# Power_Management.net
KiCad netlist of a schematic drawn in Altium Designer
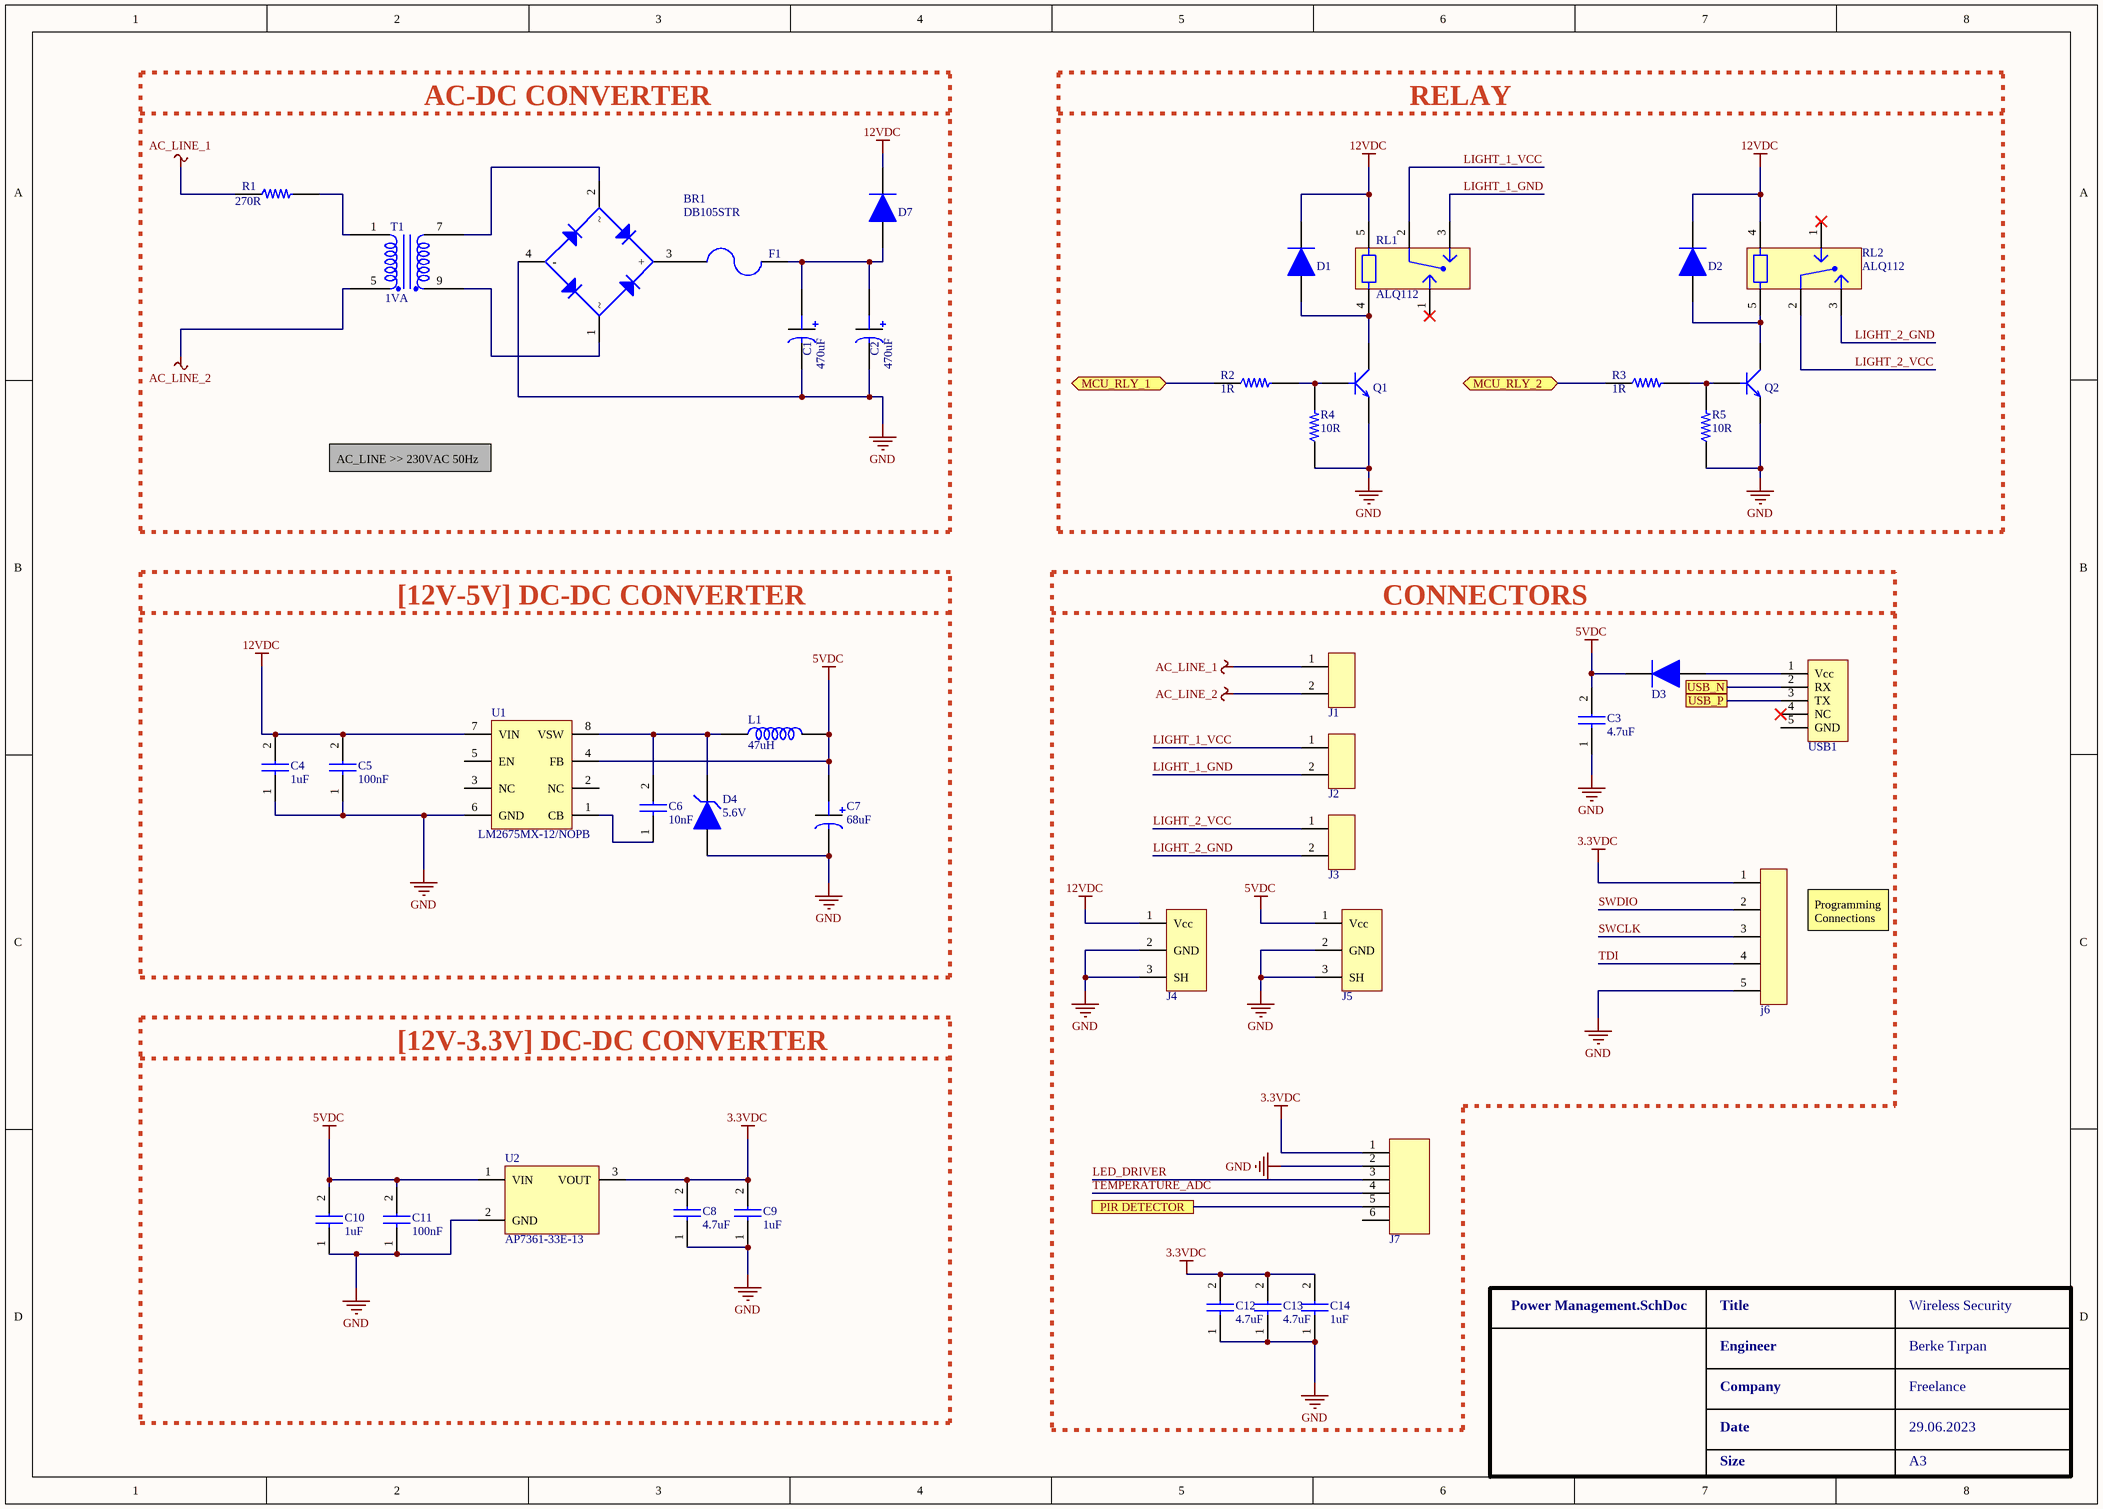
[diagram p0: Power Management.SchDoc]

(export (version "E")
  (design (tool "Eeschema 10.0.6"))
  (components
    (comp (ref "BR1")
      (value "DB105STR")
      (footprint "DB105STR")
      (description "Bridge Rect 1PHASE 600V 1A Db-s")
      (fields
        (field (name "MANUFACTURER") "Sangdest Microelectronics")
        (field (name "MANUFACTURER PART NUMBER") "DB105S")
      )
      (libsource (lib "Ilk Proje") (part "DB105STR"))
    )
    (comp (ref "C1")
      (value "ESH477M050AH4AA")
      (footprint "CAP_RADIAL_D10_P5")
      (description "Cap, 470UF, 50V, Alu Elec, Radial")
      (fields
        (field (name "MANUFACTURER") "KEMET")
        (field (name "TOLERANCE") "20%")
        (field (name "CAPACITANCE") "470uF")
      )
      (libsource (lib "Ilk Proje") (part "CAP ALU ELEC 470.UF 50V"))
    )
    (comp (ref "C2")
      (value "ESH477M050AH4AA")
      (footprint "CAP_RADIAL_D10_P5")
      (description "Cap, 470UF, 50V, Alu Elec, Radial")
      (fields
        (field (name "MANUFACTURER") "KEMET")
        (field (name "TOLERANCE") "20%")
        (field (name "CAPACITANCE") "470uF")
      )
      (libsource (lib "Ilk Proje") (part "CAP ALU ELEC 470.UF 50V"))
    )
    (comp (ref "C3")
      (value "CAP_CER_4,7UF_0805")
      (footprint "CAP_0805")
      (description "CAP CER 4.7UF 25V %10 0805")
      (fields
        (field (name "MANUFACTURER") "Samsung")
        (field (name "MANUFACTURER PART NUMBER") "CL21A475KAQNNNE")
        (field (name "CAPACITANCE") "4.7uF")
      )
      (libsource (lib "Ilk Proje") (part "CAP_CER_4,7UF_0805"))
    )
    (comp (ref "C4")
      (value "CAP CER 1uF 0805")
      (footprint "CAP_0805")
      (description "CAP CER 1UF 50V X7R %10 0805")
      (fields
        (field (name "MANUFACTURER") "Samsung")
        (field (name "MANUFACTURER PART NUMBER") "CL21B105KBFNNNE")
        (field (name "CAPACITANCE") "1uF")
      )
      (libsource (lib "Ilk Proje") (part "CAP CER 1uF 0805"))
    )
    (comp (ref "C5")
      (value "CAP CER 100nF 0805")
      (footprint "CAP_0805")
      (description "CAP CER 0.1UF 50V X7R 0805")
      (fields
        (field (name "MANUFACTURER") "Samsung")
        (field (name "MANUFACTURER PART NUMBER") "CL21B104KBCNNNC")
        (field (name "CAPACITANCE") "100nF")
      )
      (libsource (lib "Ilk Proje") (part "CAP CER 100nF 0805"))
    )
    (comp (ref "C6")
      (value "CAP CER 10nF 0603")
      (footprint "CAP_0603")
      (description "Multilayer Ceramic Capacitor, 0.01 F, 10%, X7R, 16 V, 0603 [1608 Metric] RoHS Compliant: Yes")
      (fields
        (field (name "MANUFACTURER") "Walsin Technologies")
        (field (name "MANUFACTURER PART NUMBER") "0603B103K160CT")
        (field (name "CAPACITANCE") "10nF")
      )
      (libsource (lib "Ilk Proje") (part "CAP CER 10nF 0603"))
    )
    (comp (ref "C7")
      (value "EEV686M035A9HAA")
      (footprint "CAP_EEVSERIES")
      (description "Cap Aluminum Lytic 68uF 35V 20% (6.3 X 7.7mm) SMD 280mA 2000h 105C T/R")
      (fields
        (field (name "MANUFACTURER") "KEMET")
        (field (name "TOLERANCE") "20%")
        (field (name "CAPACITANCE") "68uF")
      )
      (libsource (lib "Ilk Proje") (part "CAP ALU 68uF"))
    )
    (comp (ref "C8")
      (value "CAP_CER_4,7UF_0805")
      (footprint "CAP_0805")
      (description "CAP CER 4.7UF 25V %10 0805")
      (fields
        (field (name "MANUFACTURER") "Samsung")
        (field (name "MANUFACTURER PART NUMBER") "CL21A475KAQNNNE")
        (field (name "CAPACITANCE") "4.7uF")
      )
      (libsource (lib "Ilk Proje") (part "CAP_CER_4,7UF_0805"))
    )
    (comp (ref "C9")
      (value "CAP CER 1uF 0805")
      (footprint "CAP_0805")
      (description "CAP CER 1UF 50V X7R %10 0805")
      (fields
        (field (name "MANUFACTURER") "Samsung")
        (field (name "MANUFACTURER PART NUMBER") "CL21B105KBFNNNE")
        (field (name "CAPACITANCE") "1uF")
      )
      (libsource (lib "Ilk Proje") (part "CAP CER 1uF 0805"))
    )
    (comp (ref "C10")
      (value "CAP CER 1uF 0805")
      (footprint "CAP_0805")
      (description "CAP CER 1UF 50V X7R %10 0805")
      (fields
        (field (name "MANUFACTURER") "Samsung")
        (field (name "MANUFACTURER PART NUMBER") "CL21B105KBFNNNE")
        (field (name "CAPACITANCE") "1uF")
      )
      (libsource (lib "Ilk Proje") (part "CAP CER 1uF 0805"))
    )
    (comp (ref "C11")
      (value "C0603C104K5RACTU")
      (footprint "CAP_0603")
      (description "Multilayer Ceramic Capacitors (MLCC) - SMD/SMT 50volts 0.1uF X7R 10%")
      (fields
        (field (name "MANUFACTURER") "KEMET")
        (field (name "TOLERANCE") "10%")
        (field (name "CAPACITANCE") "100nF")
      )
      (libsource (lib "Ilk Proje") (part "CAP CER 100nF 0603"))
    )
    (comp (ref "C12")
      (value "CAP_CER_4,7UF_0805")
      (footprint "CAP_0805")
      (description "CAP CER 4.7UF 25V %10 0805")
      (fields
        (field (name "MANUFACTURER") "Samsung")
        (field (name "MANUFACTURER PART NUMBER") "CL21A475KAQNNNE")
        (field (name "CAPACITANCE") "4.7uF")
      )
      (libsource (lib "Ilk Proje") (part "CAP_CER_4,7UF_0805"))
    )
    (comp (ref "C13")
      (value "CAP_CER_4,7UF_0805")
      (footprint "CAP_0805")
      (description "CAP CER 4.7UF 25V %10 0805")
      (fields
        (field (name "MANUFACTURER") "Samsung")
        (field (name "MANUFACTURER PART NUMBER") "CL21A475KAQNNNE")
        (field (name "CAPACITANCE") "4.7uF")
      )
      (libsource (lib "Ilk Proje") (part "CAP_CER_4,7UF_0805"))
    )
    (comp (ref "C14")
      (value "CAP CER 1uF 0805")
      (footprint "CAP_0805")
      (description "CAP CER 1UF 50V X7R %10 0805")
      (fields
        (field (name "MANUFACTURER") "Samsung")
        (field (name "MANUFACTURER PART NUMBER") "CL21B105KBFNNNE")
        (field (name "CAPACITANCE") "1uF")
      )
      (libsource (lib "Ilk Proje") (part "CAP CER 1uF 0805"))
    )
    (comp (ref "D1")
      (value "1N4148WS")
      (footprint "SOD323F")
      (description "VR=75V IF=150mA Trr=4ns P=200mW")
      (fields (field (name "MANUFACTURER") "ON Semiconductor / Fairchild"))
      (libsource (lib "Ilk Proje") (part "1N4148WS"))
    )
    (comp (ref "D2")
      (value "1N4148WS")
      (footprint "SOD323F")
      (description "VR=75V IF=150mA Trr=4ns P=200mW")
      (fields (field (name "MANUFACTURER") "ON Semiconductor / Fairchild"))
      (libsource (lib "Ilk Proje") (part "1N4148WS"))
    )
    (comp (ref "D3")
      (value "1N4148WS")
      (footprint "SOD323F")
      (description "VR=75V IF=150mA Trr=4ns P=200mW")
      (fields (field (name "MANUFACTURER") "ON Semiconductor / Fairchild"))
      (libsource (lib "Ilk Proje") (part "1N4148WS"))
    )
    (comp (ref "D4")
      (value "1SMB5919BT3G")
      (footprint "SMB")
      (description "Vz=5.6V 5.32V~5.88V Izt=66.9mA")
      (fields
        (field (name "MANUFACTURER") "ON Semiconductor")
        (field (name "TOLERANCE") "5%")
        (field (name "ZENER VOLTAGE") "5.6V")
      )
      (libsource (lib "Ilk Proje") (part "1SMB5919BT3G"))
    )
    (comp (ref "D7")
      (value "1N4148WS")
      (footprint "SOD323F")
      (description "VR=75V IF=150mA Trr=4ns P=200mW")
      (fields (field (name "MANUFACTURER") "ON Semiconductor / Fairchild"))
      (libsource (lib "Ilk Proje") (part "1N4148WS"))
    )
    (comp (ref "F1")
      (value "FUSE 3413.0216.22")
      (footprint "3413.0216.22")
      (description "Fuse Chip Fast Acting 1A 32V SMD Solder Pad 1206 Glass T/R VDE/cULus")
      (fields
        (field (name "MANUFACTURER") "Schurter")
        (field (name "MANUFACTURER PART NUMBER") "3413.0216.22")
      )
      (libsource (lib "Ilk Proje") (part "FUSE 3413.0216.22"))
    )
    (comp (ref "J1")
      (value "TBP01R1-508-02BE")
      (footprint "TBP01R1-508")
      (description "2~24 Poles, Pluggable, Receptacle, Horizontal, 5.08 Pitch, Terminal Block Connector")
      (fields (field (name "MANUFACTURER") "CUI"))
      (libsource (lib "Ilk Proje") (part "TBP01R1-508-02BE"))
    )
    (comp (ref "J2")
      (value "TBP01R1-508-02BE")
      (footprint "TBP01R1-508")
      (description "2~24 Poles, Pluggable, Receptacle, Horizontal, 5.08 Pitch, Terminal Block Connector")
      (fields (field (name "MANUFACTURER") "CUI"))
      (libsource (lib "Ilk Proje") (part "TBP01R1-508-02BE"))
    )
    (comp (ref "J3")
      (value "TBP01R1-508-02BE")
      (footprint "TBP01R1-508")
      (description "2~24 Poles, Pluggable, Receptacle, Horizontal, 5.08 Pitch, Terminal Block Connector")
      (fields (field (name "MANUFACTURER") "CUI"))
      (libsource (lib "Ilk Proje") (part "TBP01R1-508-02BE"))
    )
    (comp (ref "J4")
      (value "PJ-037AH-SMT-TR")
      (footprint "JACK")
      (description "2.0 x 6.3 mm, 5.0 A, Horizontal, Surface Mount (SMT), Dc Power Jack Connector")
      (fields (field (name "MANUFACTURER") "CUI"))
      (libsource (lib "Ilk Proje") (part "PJ-037AH-SMT-TR"))
    )
    (comp (ref "J5")
      (value "PJ-037AH-SMT-TR")
      (footprint "JACK")
      (description "2.0 x 6.3 mm, 5.0 A, Horizontal, Surface Mount (SMT), Dc Power Jack Connector")
      (fields (field (name "MANUFACTURER") "CUI"))
      (libsource (lib "Ilk Proje") (part "PJ-037AH-SMT-TR"))
    )
    (comp (ref "j6")
      (value "SMH-105-02-L-S")
      (footprint "PINHEADER1X5_RA")
      (description ".100 C.L. HORIZONTAL SMT SOCKET")
      (fields (field (name "MANUFACTURER") "Samtec"))
      (libsource (lib "Ilk Proje") (part "SMH-105-02-L-S"))
    )
    (comp (ref "J7")
      (value "64800611622")
      (footprint "64800611622")
      (description "WR-WTB Wire-to-Board Connectors 6PIN 1.50 mm")
      (fields (field (name "MANUFACTURER") "Wurth Electronics"))
      (libsource (lib "Ilk Proje") (part "64800611622_conn_6pin"))
    )
    (comp (ref "L1")
      (value "78438335470")
      (footprint "IND_1212")
      (description "Power Inductor, Aec-Q200, 47Uh, 0.39A Rohs Compliant: Yes ¦Wurth Elektronik 78438335470")
      (fields
        (field (name "MANUFACTURER") "Wurth Electronics")
        (field (name "TOLERANCE") "30%")
        (field (name "INDUCTANCE") "47uH")
      )
      (libsource (lib "Ilk Proje") (part "IND 47uH"))
    )
    (comp (ref "Q1")
      (value "MMBT3904-7-F")
      (footprint "SOT23-F")
      (description "NPN Ic=200mA Vceo=40V hfe=100~300 fT=310MHz P=300mW SOT-23")
      (fields (field (name "MANUFACTURER") "Diodes Zetex"))
      (libsource (lib "Ilk Proje") (part "MMBT3904-7-F"))
    )
    (comp (ref "Q2")
      (value "MMBT3904-7-F")
      (footprint "SOT23-F")
      (description "NPN Ic=200mA Vceo=40V hfe=100~300 fT=310MHz P=300mW SOT-23")
      (fields (field (name "MANUFACTURER") "Diodes Zetex"))
      (libsource (lib "Ilk Proje") (part "MMBT3904-7-F"))
    )
    (comp (ref "R1")
      (value "5WD27")
      (footprint "RES_AXIAL_W")
      (description "RES 0.27 OHM 5% 5W AXIAL")
      (fields
        (field (name "MFR") "NTE Electronics, Inc")
        (field (name "TOLERANCE") "±5%")
        (field (name "RESISTANCE") "270R")
      )
      (libsource (lib "Ilk Proje") (part "5WD27"))
    )
    (comp (ref "R2")
      (value "RT0603BRD071KL")
      (footprint "RES_0603")
      (description "High Precision-High Stability Chip Resistor Thin Film 0603 1kOhm 0.1% Paper T/R")
      (fields (field (name "MANUFACTURER") "Yageo") (field (name "RESISTANCE") "1R"))
      (libsource (lib "Ilk Proje") (part "RES 1K OHM 0603"))
    )
    (comp (ref "R3")
      (value "RT0603BRD071KL")
      (footprint "RES_0603")
      (description "High Precision-High Stability Chip Resistor Thin Film 0603 1kOhm 0.1% Paper T/R")
      (fields (field (name "MANUFACTURER") "Yageo") (field (name "RESISTANCE") "1R"))
      (libsource (lib "Ilk Proje") (part "RES 1K OHM 0603"))
    )
    (comp (ref "R4")
      (value "RC0603FR-0710KL")
      (footprint "RES_0603")
      (description "RES SMD 10K OHM 1% 1/10W 0603")
      (fields
        (field (name "MANUFACTURER") "Yageo")
        (field (name "TOLERANCE") "1%")
        (field (name "RESISTANCE") "10R")
      )
      (libsource (lib "Ilk Proje") (part "RES 10K OHM 0603"))
    )
    (comp (ref "R5")
      (value "RC0603FR-0710KL")
      (footprint "RES_0603")
      (description "RES SMD 10K OHM 1% 1/10W 0603")
      (fields
        (field (name "MANUFACTURER") "Yageo")
        (field (name "TOLERANCE") "1%")
        (field (name "RESISTANCE") "10R")
      )
      (libsource (lib "Ilk Proje") (part "RES 10K OHM 0603"))
    )
    (comp (ref "RL1")
      (value "ALQ112")
      (footprint "ALQ112")
      (description "General Purpose Relay SPDT (1 Form C) 12VDC Coil Through Hole")
      (fields (field (name "MANUFACTURER") "Panasonic"))
      (libsource (lib "") (part "ALQ112_1"))
    )
    (comp (ref "RL2")
      (value "ALQ112")
      (footprint "ALQ112")
      (description "General Purpose Relay SPDT (1 Form C) 12VDC Coil Through Hole")
      (fields (field (name "MANUFACTURER") "Panasonic"))
      (libsource (lib "Ilk Proje") (part "ALQ112"))
    )
    (comp (ref "T1")
      (value "BV302S12010-ZU")
      (footprint "BV302S12010-ZU")
      (description "230-12V Transformer 1VA")
      (fields (field (name "MANUFACTURER") "Zettler Magnetics") (field (name "RATED POWER") "1VA"))
      (libsource (lib "Ilk Proje") (part "BV302S12010-ZU"))
    )
    (comp (ref "U1")
      (value "LM2675MX-12/NOPB")
      (footprint "SOIC8")
      (description "SIMPLE SWITCHER® 6.5V to 40V, 1A Low Component Count Step-Down Regulator 8-SOIC -40 to 125")
      (fields (field (name "MANUFACTURER") "TI National Semiconductor"))
      (libsource (lib "Ilk Proje") (part "LM2675MX-12/NOPB"))
    )
    (comp (ref "U2")
      (value "AP7361-33E-13")
      (footprint "SOT223")
      (description "AP7361 Series 3.3 V 1 A Low SMT Dropout Fixed-Mode Regulator - SOT-223")
      (fields (field (name "MANUFACTURER") "Diodes"))
      (libsource (lib "Ilk Proje") (part "AP7361-33E-13"))
    )
    (comp (ref "USB1")
      (value "10118192-0001LF")
      (footprint "MICRO_B_USB")
      (description "CONN USB MICRO B RECPT SMT R/A")
      (fields (field (name "MANUFACTURER") "Amphenol ICC / FCI"))
      (libsource (lib "Ilk Proje") (part "Micro B USB Connector"))
    )
  )
  (nets
    (net (code "1") (name "/LED_DRIVER") (class "Default") (node (ref "J7") (pin "3") (pintype "power_in")))
    (net (code "2") (name "/LIGHT_1_GND") (class "Default")
      (node (ref "J2") (pin "2") (pinfunction "2_2") (pintype "power_in"))
      (node (ref "RL1") (pin "3") (pinfunction "3_3") (pintype "passive"))
    )
    (net (code "3") (name "/LIGHT_1_VCC") (class "Default")
      (node (ref "J2") (pin "1") (pinfunction "1_1") (pintype "power_in"))
      (node (ref "RL1") (pin "2") (pinfunction "2_2") (pintype "passive"))
    )
    (net (code "4") (name "/LIGHT_2_GND") (class "Default")
      (node (ref "J3") (pin "2") (pinfunction "2_2") (pintype "power_in"))
      (node (ref "RL2") (pin "3") (pinfunction "3_3") (pintype "passive"))
    )
    (net (code "5") (name "/LIGHT_2_VCC") (class "Default")
      (node (ref "J3") (pin "1") (pinfunction "1_1") (pintype "power_in"))
      (node (ref "RL2") (pin "2") (pinfunction "2_2") (pintype "passive"))
    )
    (net (code "6") (name "/MCU_RLY_1") (class "Default")
      (node (ref "R2") (pin "1") (pinfunction "1_1") (pintype "passive"))
    )
    (net (code "7") (name "/MCU_RLY_2") (class "Default")
      (node (ref "R3") (pin "1") (pinfunction "1_1") (pintype "passive"))
    )
    (net (code "8") (name "/PIR DETECTOR") (class "Default") (node (ref "J7") (pin "5") (pintype "power_in")))
    (net (code "9") (name "/SWCLK") (class "Default")
      (node (ref "j6") (pin "3") (pinfunction "3_3") (pintype "power_in"))
    )
    (net (code "10") (name "/SWDIO") (class "Default")
      (node (ref "j6") (pin "2") (pinfunction "2_2") (pintype "power_in"))
    )
    (net (code "11") (name "/TDI") (class "Default")
      (node (ref "j6") (pin "4") (pinfunction "4_4") (pintype "power_in"))
    )
    (net (code "12") (name "/TEMPERATURE_ADC") (class "Default")
      (node (ref "J7") (pin "4") (pintype "power_in"))
    )
    (net (code "13") (name "/USB_N") (class "Default")
      (node (ref "USB1") (pin "2") (pinfunction "RX_2") (pintype "power_in"))
    )
    (net (code "14") (name "/USB_P") (class "Default")
      (node (ref "USB1") (pin "3") (pinfunction "TX_3") (pintype "power_in"))
    )
    (net (code "15") (name "3.3VDC") (class "Default")
      (node (ref "C12") (pin "2") (pinfunction "2_2") (pintype "passive"))
      (node (ref "C13") (pin "2") (pinfunction "2_2") (pintype "passive"))
      (node (ref "C14") (pin "2") (pinfunction "2_2") (pintype "passive"))
      (node (ref "C8") (pin "2") (pinfunction "2_2") (pintype "passive"))
      (node (ref "C9") (pin "2") (pinfunction "2_2") (pintype "passive"))
      (node (ref "J7") (pin "1") (pintype "power_in"))
      (node (ref "U2") (pin "3") (pinfunction "VOUT_3") (pintype "passive"))
      (node (ref "j6") (pin "1") (pinfunction "1_1") (pintype "power_in"))
    )
    (net (code "16") (name "5VDC") (class "Default")
      (node (ref "C10") (pin "2") (pinfunction "2_2") (pintype "passive"))
      (node (ref "C11") (pin "2") (pinfunction "2_2") (pintype "passive"))
      (node (ref "C3") (pin "2") (pinfunction "2_2") (pintype "passive"))
      (node (ref "C7") (pin "1") (pinfunction "1_1") (pintype "passive"))
      (node (ref "D3") (pin "1") (pinfunction "1_1") (pintype "power_in"))
      (node (ref "J5") (pin "1") (pinfunction "Vcc_1") (pintype "passive"))
      (node (ref "L1") (pin "2") (pinfunction "2_2") (pintype "passive"))
      (node (ref "U1") (pin "4") (pinfunction "FB_4") (pintype "passive"))
      (node (ref "U2") (pin "1") (pinfunction "VIN_1") (pintype "passive"))
    )
    (net (code "17") (name "12VDC") (class "Default")
      (node (ref "C4") (pin "2") (pinfunction "2_2") (pintype "passive"))
      (node (ref "C5") (pin "2") (pinfunction "2_2") (pintype "passive"))
      (node (ref "D1") (pin "1") (pinfunction "1_1") (pintype "power_in"))
      (node (ref "D2") (pin "1") (pinfunction "1_1") (pintype "power_in"))
      (node (ref "D7") (pin "1") (pinfunction "1_1") (pintype "power_in"))
      (node (ref "J4") (pin "1") (pinfunction "Vcc_1") (pintype "passive"))
      (node (ref "RL1") (pin "5") (pinfunction "5_5") (pintype "passive"))
      (node (ref "RL2") (pin "4") (pinfunction "4_4") (pintype "passive"))
      (node (ref "U1") (pin "7") (pinfunction "VIN_7") (pintype "passive"))
    )
    (net (code "18") (name "AC_LINE_1") (class "Default")
      (node (ref "J1") (pin "1") (pinfunction "1_1") (pintype "power_in"))
      (node (ref "R1") (pin "1") (pinfunction "1_1") (pintype "passive"))
    )
    (net (code "19") (name "AC_LINE_2") (class "Default")
      (node (ref "J1") (pin "2") (pinfunction "2_2") (pintype "power_in"))
      (node (ref "T1") (pin "5") (pinfunction "5_5") (pintype "passive"))
    )
    (net (code "20") (name "GND") (class "Default")
      (node (ref "BR1") (pin "4") (pinfunction "-_4") (pintype "passive"))
      (node (ref "C1") (pin "2") (pinfunction "2_2") (pintype "passive"))
      (node (ref "C10") (pin "1") (pinfunction "1_1") (pintype "passive"))
      (node (ref "C11") (pin "1") (pinfunction "1_1") (pintype "passive"))
      (node (ref "C12") (pin "1") (pinfunction "1_1") (pintype "passive"))
      (node (ref "C13") (pin "1") (pinfunction "1_1") (pintype "passive"))
      (node (ref "C14") (pin "1") (pinfunction "1_1") (pintype "passive"))
      (node (ref "C2") (pin "2") (pinfunction "2_2") (pintype "passive"))
      (node (ref "C3") (pin "1") (pinfunction "1_1") (pintype "passive"))
      (node (ref "C4") (pin "1") (pinfunction "1_1") (pintype "passive"))
      (node (ref "C5") (pin "1") (pinfunction "1_1") (pintype "passive"))
      (node (ref "C7") (pin "2") (pinfunction "2_2") (pintype "passive"))
      (node (ref "C8") (pin "1") (pinfunction "1_1") (pintype "passive"))
      (node (ref "C9") (pin "1") (pinfunction "1_1") (pintype "passive"))
      (node (ref "D4") (pin "A") (pinfunction "A_A") (pintype "passive"))
      (node (ref "J4") (pin "2") (pinfunction "GND_2") (pintype "passive"))
      (node (ref "J4") (pin "3") (pinfunction "SH_3") (pintype "passive"))
      (node (ref "J5") (pin "2") (pinfunction "GND_2") (pintype "passive"))
      (node (ref "J5") (pin "3") (pinfunction "SH_3") (pintype "passive"))
      (node (ref "J7") (pin "2") (pintype "power_in"))
      (node (ref "Q1") (pin "2") (pinfunction "E_2") (pintype "power_in"))
      (node (ref "Q2") (pin "2") (pinfunction "E_2") (pintype "power_in"))
      (node (ref "R4") (pin "1") (pinfunction "1_1") (pintype "passive"))
      (node (ref "R5") (pin "1") (pinfunction "1_1") (pintype "passive"))
      (node (ref "U1") (pin "6") (pinfunction "GND_6") (pintype "passive"))
      (node (ref "U2") (pin "2") (pinfunction "GND_2") (pintype "passive"))
      (node (ref "j6") (pin "5") (pinfunction "5_5") (pintype "power_in"))
    )
    (net (code "21") (name "Net-(BR1-+)") (class "Default")
      (node (ref "BR1") (pin "3") (pinfunction "+_3") (pintype "passive"))
      (node (ref "F1") (pin "1") (pinfunction "1_1") (pintype "passive"))
    )
    (net (code "22") (name "Net-(BR1-~-Pad1)") (class "Default")
      (node (ref "BR1") (pin "1") (pinfunction "~_1") (pintype "passive"))
      (node (ref "T1") (pin "9") (pinfunction "9_9") (pintype "passive"))
    )
    (net (code "23") (name "Net-(BR1-~-Pad2)") (class "Default")
      (node (ref "BR1") (pin "2") (pinfunction "~_2") (pintype "passive"))
      (node (ref "T1") (pin "7") (pinfunction "7_7") (pintype "passive"))
    )
    (net (code "24") (name "Net-(C1-Pad1)") (class "Default")
      (node (ref "C1") (pin "1") (pinfunction "1_1") (pintype "passive"))
      (node (ref "C2") (pin "1") (pinfunction "1_1") (pintype "passive"))
      (node (ref "D7") (pin "2") (pinfunction "2_2") (pintype "power_in"))
      (node (ref "F1") (pin "2") (pinfunction "2_2") (pintype "passive"))
    )
    (net (code "25") (name "Net-(Q1-B)") (class "Default")
      (node (ref "Q1") (pin "1") (pinfunction "B_1") (pintype "power_in"))
      (node (ref "R2") (pin "2") (pinfunction "2_2") (pintype "passive"))
      (node (ref "R4") (pin "2") (pinfunction "2_2") (pintype "passive"))
    )
    (net (code "26") (name "Net-(Q1-C)") (class "Default")
      (node (ref "D1") (pin "2") (pinfunction "2_2") (pintype "power_in"))
      (node (ref "Q1") (pin "3") (pinfunction "C_3") (pintype "power_in"))
      (node (ref "RL1") (pin "4") (pinfunction "4_4") (pintype "passive"))
    )
    (net (code "27") (name "Net-(Q2-B)") (class "Default")
      (node (ref "Q2") (pin "1") (pinfunction "B_1") (pintype "power_in"))
      (node (ref "R3") (pin "2") (pinfunction "2_2") (pintype "passive"))
      (node (ref "R5") (pin "2") (pinfunction "2_2") (pintype "passive"))
    )
    (net (code "28") (name "Net-(Q2-C)") (class "Default")
      (node (ref "D2") (pin "2") (pinfunction "2_2") (pintype "power_in"))
      (node (ref "Q2") (pin "3") (pinfunction "C_3") (pintype "power_in"))
      (node (ref "RL2") (pin "5") (pinfunction "5_5") (pintype "passive"))
    )
    (net (code "29") (name "Net-(R1-Pad2)") (class "Default")
      (node (ref "R1") (pin "2") (pinfunction "2_2") (pintype "passive"))
      (node (ref "T1") (pin "1") (pinfunction "1_1") (pintype "passive"))
    )
    (net (code "30") (name "Net-(U1-CB)") (class "Default")
      (node (ref "C6") (pin "1") (pinfunction "1_1") (pintype "passive"))
      (node (ref "U1") (pin "1") (pinfunction "CB_1") (pintype "passive"))
    )
    (net (code "31") (name "Net-(U1-VSW)") (class "Default")
      (node (ref "C6") (pin "2") (pinfunction "2_2") (pintype "passive"))
      (node (ref "D4") (pin "C") (pinfunction "C_C") (pintype "passive"))
      (node (ref "L1") (pin "1") (pinfunction "1_1") (pintype "passive"))
      (node (ref "U1") (pin "8") (pinfunction "VSW_8") (pintype "passive"))
    )
    (net (code "32") (name "Net-(USB1-Vcc)") (class "Default")
      (node (ref "D3") (pin "2") (pinfunction "2_2") (pintype "power_in"))
      (node (ref "USB1") (pin "1") (pinfunction "Vcc_1") (pintype "power_in"))
    )
    (net (code "33") (name "unconnected-(J7-Pad6)") (class "Default")
      (node (ref "J7") (pin "6") (pintype "power_in"))
    )
    (net (code "34") (name "unconnected-(RL1-Pad1)") (class "Default")
      (node (ref "RL1") (pin "1") (pinfunction "1_1") (pintype "passive+no_connect"))
    )
    (net (code "35") (name "unconnected-(RL2-Pad1)") (class "Default")
      (node (ref "RL2") (pin "1") (pinfunction "1_1") (pintype "passive+no_connect"))
    )
    (net (code "36") (name "unconnected-(U1-EN-Pad5)") (class "Default")
      (node (ref "U1") (pin "5") (pinfunction "EN_5") (pintype "passive"))
    )
    (net (code "37") (name "unconnected-(U1-NC-Pad2)") (class "Default")
      (node (ref "U1") (pin "2") (pinfunction "NC_2") (pintype "passive"))
    )
    (net (code "38") (name "unconnected-(U1-NC-Pad3)") (class "Default")
      (node (ref "U1") (pin "3") (pinfunction "NC_3") (pintype "passive"))
    )
    (net (code "39") (name "unconnected-(USB1-GND-Pad5)") (class "Default")
      (node (ref "USB1") (pin "5") (pinfunction "GND_5") (pintype "power_in"))
    )
    (net (code "40") (name "unconnected-(USB1-NC-Pad4)") (class "Default")
      (node (ref "USB1") (pin "4") (pinfunction "NC_4") (pintype "power_in+no_connect"))
    )
  )
)
